# Tray2_Comms_SwC.net
KiCad netlist of a schematic drawn in Altium Designer
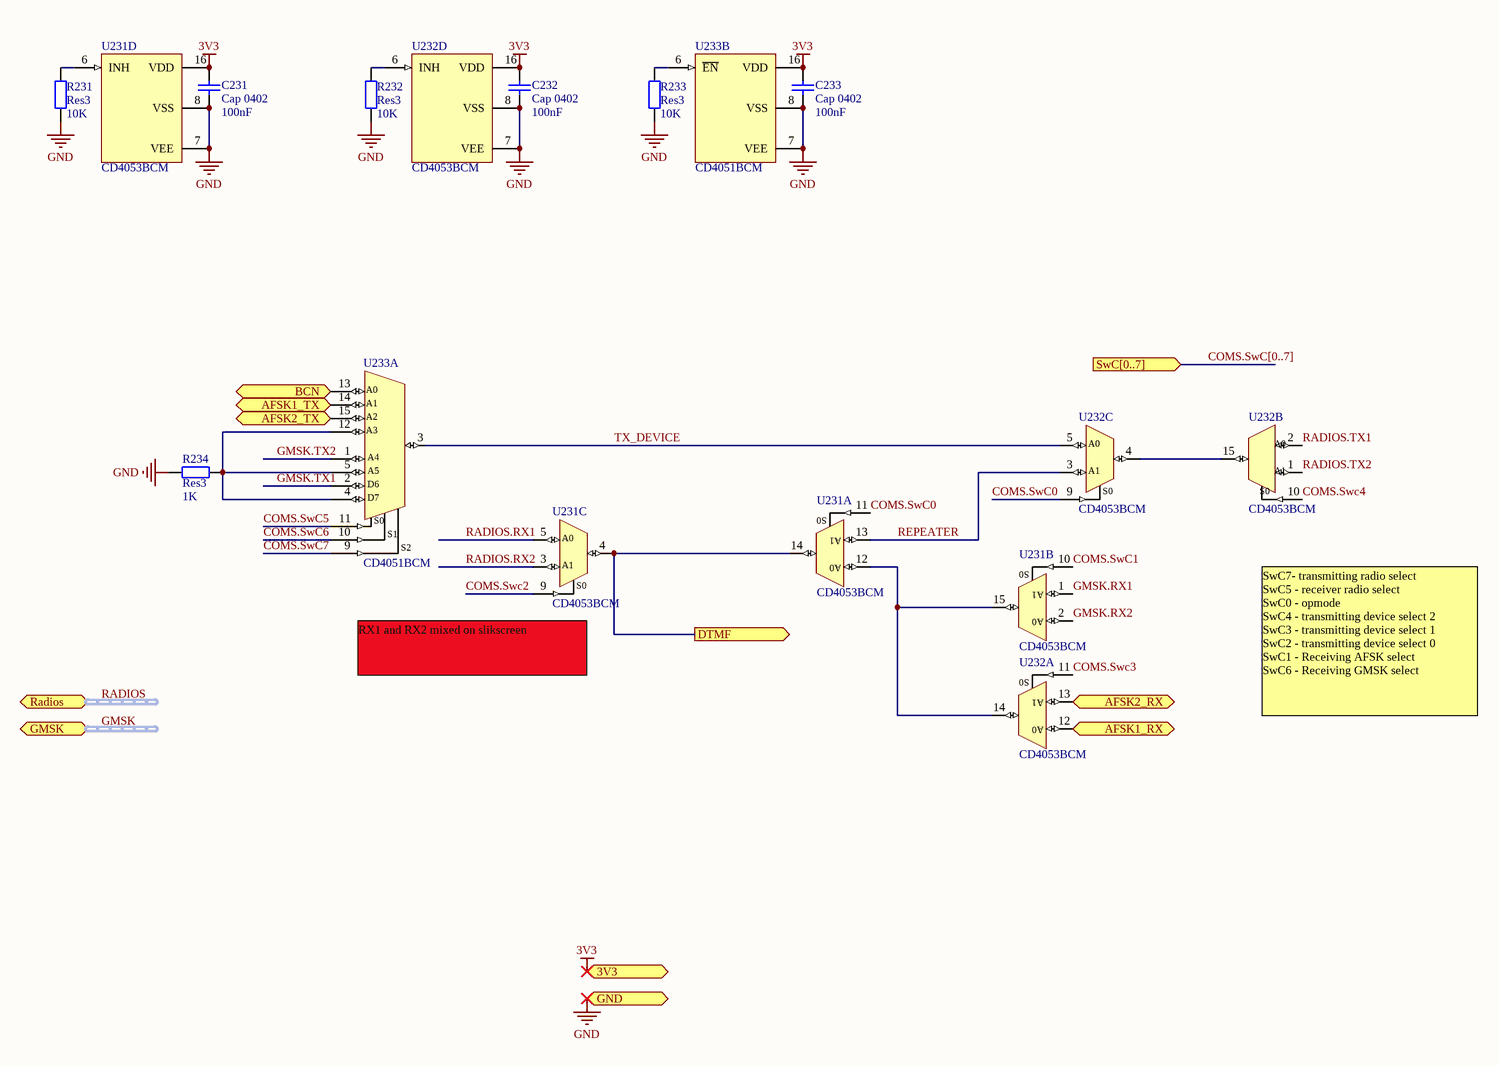
[diagram p0: Tray2_Comms_SwC.SchDoc]

(export (version "E")
  (design (tool "Eeschema 10.0.6"))
  (components
    (comp (ref "C231")
      (value "Cap 0402")
      (footprint "CAPC1005X06L")
      (description "Capacitor")
      (fields (field (name "ALTIUM_VALUE") "100nF") (field (name "PUBLISHER") "Altium Limited"))
      (libsource (lib "CSC") (part "Cap 0402"))
    )
    (comp (ref "C232")
      (value "Cap 0402")
      (footprint "CAPC1005X06L")
      (description "Capacitor")
      (fields (field (name "ALTIUM_VALUE") "100nF") (field (name "PUBLISHER") "Altium Limited"))
      (libsource (lib "CSC") (part "Cap 0402"))
    )
    (comp (ref "C233")
      (value "Cap 0402")
      (footprint "CAPC1005X06L")
      (description "Capacitor")
      (fields (field (name "ALTIUM_VALUE") "100nF") (field (name "PUBLISHER") "Altium Limited"))
      (libsource (lib "CSC") (part "Cap 0402"))
    )
    (comp (ref "R231")
      (value "Res3")
      (footprint "RESC1005X06L")
      (description "Resistor")
      (fields (field (name "ALTIUM_VALUE") "10K") (field (name "PUBLISHER") "Altium Limited"))
      (libsource (lib "CSC") (part "Res3"))
    )
    (comp (ref "R232")
      (value "Res3")
      (footprint "RESC1005X06L")
      (description "Resistor")
      (fields (field (name "ALTIUM_VALUE") "10K") (field (name "PUBLISHER") "Altium Limited"))
      (libsource (lib "CSC") (part "Res3"))
    )
    (comp (ref "R233")
      (value "Res3")
      (footprint "RESC1005X06L")
      (description "Resistor")
      (fields (field (name "ALTIUM_VALUE") "10K") (field (name "PUBLISHER") "Altium Limited"))
      (libsource (lib "CSC") (part "Res3"))
    )
    (comp (ref "R234")
      (value "Res3")
      (footprint "RESC1005X06L")
      (description "Resistor")
      (fields (field (name "ALTIUM_VALUE") "1K") (field (name "PUBLISHER") "Altium Limited"))
      (libsource (lib "") (part "Res3_1"))
    )
    (comp (ref "U231")
      (value "CD4053BCM")
      (footprint "Comms Board Small Footprints:TSSOP16")
      (description "Triple 2-Channnel Analog Multiplexer/Demutiplexer")
      (libsource (lib "") (part "CD4053BCM_1"))
    )
    (comp (ref "U232")
      (value "CD4053BCM")
      (footprint "Comms Board Small Footprints:TSSOP16")
      (description "Triple 2-Channnel Analog Multiplexer/Demutiplexer")
      (libsource (lib "Comms Board Small Footprints") (part "CD4053BCM"))
    )
    (comp (ref "U233")
      (value "CD4051BCM")
      (footprint "Comms Board Small Footprints:TSSOP16")
      (description "8-Channel Analog Multiplexer/Demultiplexer")
      (libsource (lib "") (part "CD4051BCM_1"))
    )
  )
  (nets
    (net (code "6") (name "/AFSK1_RX") (class "Default")
      (node (ref "U232") (pin "12") (pinfunction "A0_12") (pintype "bidirectional"))
    )
    (net (code "7") (name "/AFSK1_TX") (class "Default")
      (node (ref "U233") (pin "14") (pinfunction "A1_14") (pintype "bidirectional"))
    )
    (net (code "8") (name "/AFSK2_RX") (class "Default")
      (node (ref "U232") (pin "13") (pinfunction "A1_13") (pintype "bidirectional"))
    )
    (net (code "9") (name "/AFSK2_TX") (class "Default")
      (node (ref "U233") (pin "15") (pinfunction "A2_15") (pintype "bidirectional"))
    )
    (net (code "10") (name "/BCN") (class "Default")
      (node (ref "U233") (pin "13") (pinfunction "A0_13") (pintype "bidirectional"))
    )
    (net (code "11") (name "/COMS.SwC0") (class "Default")
      (node (ref "U231") (pin "11") (pinfunction "A_11") (pintype "input"))
      (node (ref "U232") (pin "9") (pinfunction "C_9") (pintype "input"))
    )
    (net (code "12") (name "/COMS.SwC1") (class "Default")
      (node (ref "U231") (pin "10") (pinfunction "B_10") (pintype "input"))
    )
    (net (code "13") (name "/COMS.SwC5") (class "Default")
      (node (ref "U233") (pin "11") (pinfunction "S0_11") (pintype "input"))
    )
    (net (code "14") (name "/COMS.SwC6") (class "Default")
      (node (ref "U233") (pin "10") (pinfunction "S1_10") (pintype "input"))
    )
    (net (code "15") (name "/COMS.SwC7") (class "Default")
      (node (ref "U233") (pin "9") (pinfunction "S2_9") (pintype "input"))
    )
    (net (code "17") (name "/COMS.Swc2") (class "Default")
      (node (ref "U231") (pin "9") (pinfunction "C_9") (pintype "input"))
    )
    (net (code "18") (name "/COMS.Swc3") (class "Default")
      (node (ref "U232") (pin "11") (pinfunction "A_11") (pintype "input"))
    )
    (net (code "19") (name "/COMS.Swc4") (class "Default")
      (node (ref "U232") (pin "10") (pinfunction "B_10") (pintype "input"))
    )
    (net (code "20") (name "/DTMF") (class "Default")
      (node (ref "U231") (pin "14") (pinfunction "A_out_14") (pintype "bidirectional"))
      (node (ref "U231") (pin "4") (pinfunction "c_out_4") (pintype "bidirectional"))
    )
    (net (code "21") (name "/GMSK.RX1") (class "Default")
      (node (ref "U231") (pin "1") (pinfunction "by_1") (pintype "bidirectional"))
    )
    (net (code "22") (name "/GMSK.RX2") (class "Default")
      (node (ref "U231") (pin "2") (pinfunction "bx_2") (pintype "bidirectional"))
    )
    (net (code "23") (name "/GMSK.TX1") (class "Default")
      (node (ref "U233") (pin "2") (pinfunction "A6_2") (pintype "bidirectional"))
    )
    (net (code "24") (name "/GMSK.TX2") (class "Default")
      (node (ref "U233") (pin "1") (pinfunction "A4_1") (pintype "bidirectional"))
    )
    (net (code "25") (name "/RADIOS.RX1") (class "Default")
      (node (ref "U231") (pin "5") (pinfunction "cx_5") (pintype "bidirectional"))
    )
    (net (code "26") (name "/RADIOS.RX2") (class "Default")
      (node (ref "U231") (pin "3") (pinfunction "cy_3") (pintype "bidirectional"))
    )
    (net (code "27") (name "/RADIOS.TX1") (class "Default")
      (node (ref "U232") (pin "2") (pinfunction "bx_2") (pintype "bidirectional"))
    )
    (net (code "28") (name "/RADIOS.TX2") (class "Default")
      (node (ref "U232") (pin "1") (pinfunction "by_1") (pintype "bidirectional"))
    )
    (net (code "29") (name "/REPEATER") (class "Default")
      (node (ref "U231") (pin "13") (pinfunction "A1_13") (pintype "bidirectional"))
      (node (ref "U232") (pin "3") (pinfunction "cy_3") (pintype "bidirectional"))
    )
    (net (code "30") (name "/TX_DEVICE") (class "Default")
      (node (ref "U232") (pin "5") (pinfunction "cx_5") (pintype "bidirectional"))
      (node (ref "U233") (pin "3") (pinfunction "O_3") (pintype "bidirectional"))
    )
    (net (code "33") (name "3V3") (class "Default")
      (node (ref "C231") (pin "2") (pinfunction "2_2") (pintype "passive"))
      (node (ref "C232") (pin "2") (pinfunction "2_2") (pintype "passive"))
      (node (ref "C233") (pin "2") (pinfunction "2_2") (pintype "passive"))
      (node (ref "U231") (pin "16") (pinfunction "VDD_16") (pintype "power_in"))
      (node (ref "U232") (pin "16") (pinfunction "VDD_16") (pintype "power_in"))
      (node (ref "U233") (pin "16") (pinfunction "VDD_16") (pintype "power_in"))
    )
    (net (code "34") (name "GND") (class "Default")
      (node (ref "C231") (pin "1") (pinfunction "1_1") (pintype "passive"))
      (node (ref "C232") (pin "1") (pinfunction "1_1") (pintype "passive"))
      (node (ref "C233") (pin "1") (pinfunction "1_1") (pintype "passive"))
      (node (ref "R231") (pin "2") (pinfunction "2_2") (pintype "passive"))
      (node (ref "R232") (pin "2") (pinfunction "2_2") (pintype "passive"))
      (node (ref "R233") (pin "2") (pinfunction "2_2") (pintype "passive"))
      (node (ref "R234") (pin "1") (pinfunction "1_1") (pintype "passive"))
      (node (ref "U231") (pin "7") (pinfunction "VEE_7") (pintype "power_in"))
      (node (ref "U231") (pin "8") (pinfunction "VSS_8") (pintype "power_in"))
      (node (ref "U232") (pin "7") (pinfunction "VEE_7") (pintype "power_in"))
      (node (ref "U232") (pin "8") (pinfunction "VSS_8") (pintype "power_in"))
      (node (ref "U233") (pin "7") (pinfunction "VEE_7") (pintype "power_in"))
      (node (ref "U233") (pin "8") (pinfunction "VSS_8") (pintype "power_in"))
    )
    (net (code "35") (name "Net-(U231A-A0)") (class "Default")
      (node (ref "U231") (pin "12") (pinfunction "A0_12") (pintype "bidirectional"))
      (node (ref "U231") (pin "15") (pinfunction "b_out_15") (pintype "bidirectional"))
      (node (ref "U232") (pin "14") (pinfunction "A_out_14") (pintype "bidirectional"))
    )
    (net (code "36") (name "Net-(U231D-INH)") (class "Default")
      (node (ref "R231") (pin "1") (pinfunction "1_1") (pintype "passive"))
      (node (ref "U231") (pin "6") (pinfunction "INH_6") (pintype "input"))
    )
    (net (code "37") (name "Net-(U232B-b_out)") (class "Default")
      (node (ref "U232") (pin "15") (pinfunction "b_out_15") (pintype "bidirectional"))
      (node (ref "U232") (pin "4") (pinfunction "c_out_4") (pintype "bidirectional"))
    )
    (net (code "38") (name "Net-(U232D-INH)") (class "Default")
      (node (ref "R232") (pin "1") (pinfunction "1_1") (pintype "passive"))
      (node (ref "U232") (pin "6") (pinfunction "INH_6") (pintype "input"))
    )
    (net (code "39") (name "Net-(U233A-A3)") (class "Default")
      (node (ref "R234") (pin "2") (pinfunction "2_2") (pintype "passive"))
      (node (ref "U233") (pin "12") (pinfunction "A3_12") (pintype "bidirectional"))
      (node (ref "U233") (pin "4") (pinfunction "A7_4") (pintype "bidirectional"))
      (node (ref "U233") (pin "5") (pinfunction "A5_5") (pintype "bidirectional"))
    )
    (net (code "40") (name "Net-(U233B-~{EN})") (class "Default")
      (node (ref "R233") (pin "1") (pinfunction "1_1") (pintype "passive"))
      (node (ref "U233") (pin "6") (pinfunction "~{EN}_6") (pintype "input"))
    )
  )
)
